# mcu_regule.net
KiCad netlist of a schematic drawn in Altium Designer
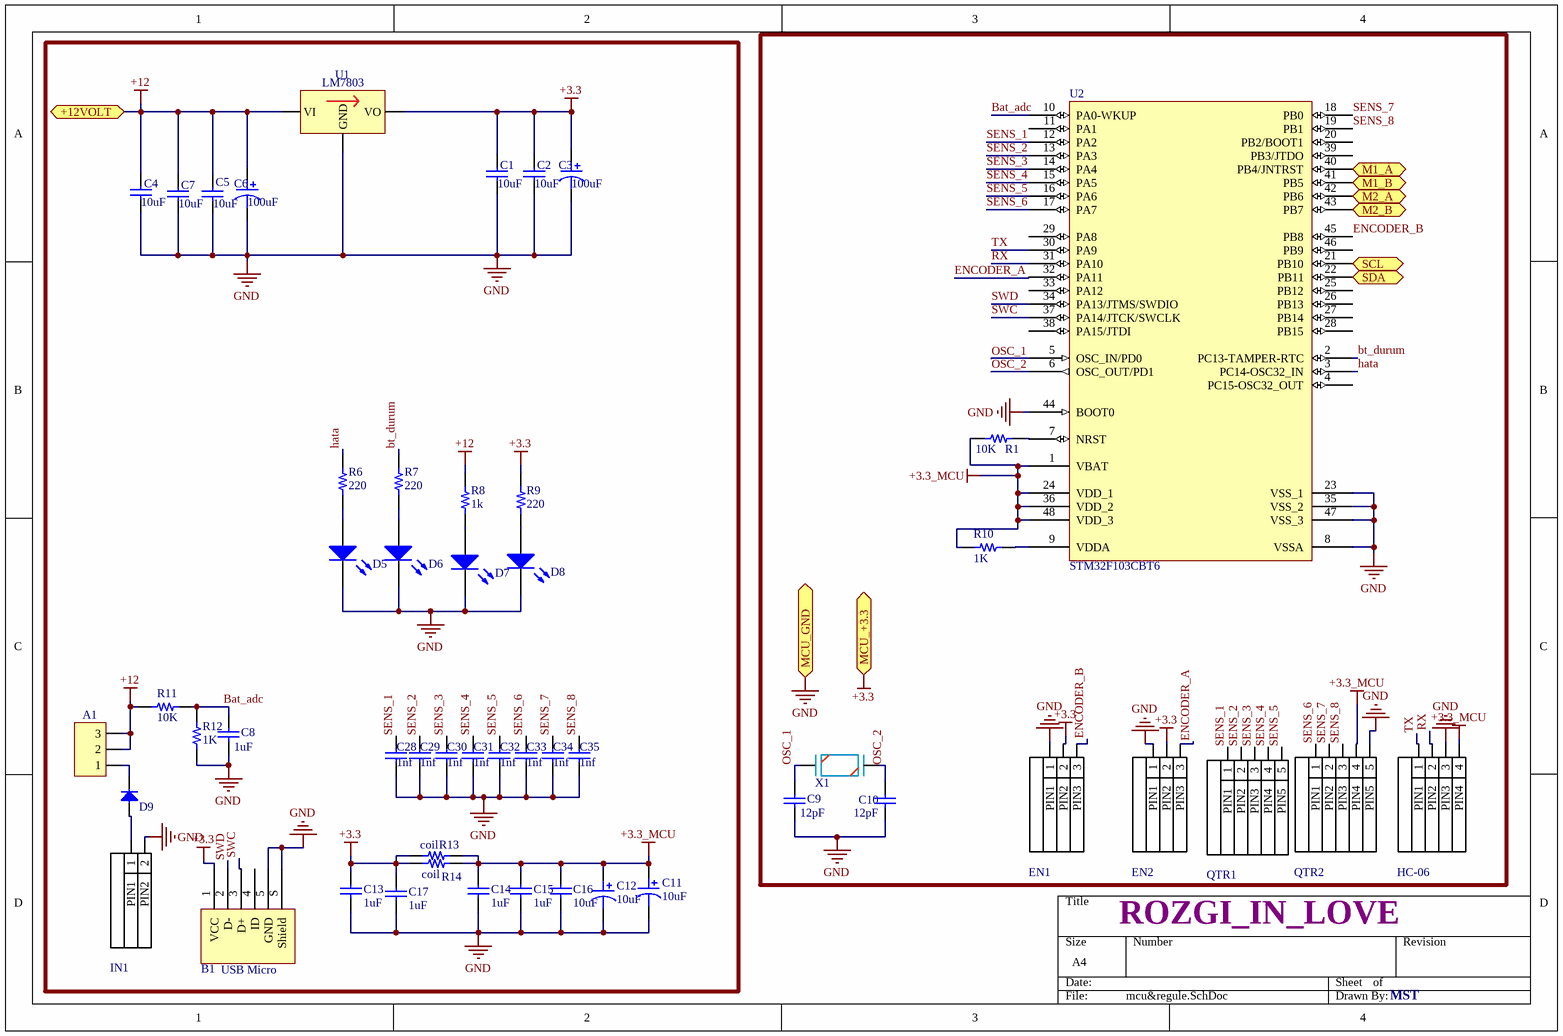
[diagram p0: mcu&regule.SchDoc]

(export (version "E")
  (design (tool "Eeschema 10.0.6"))
  (components
    (comp (ref "A1")
      (value "anahtar")
      (footprint "MSS22D18 Switch")
      (libsource (lib "genel") (part "anahtarlar"))
    )
    (comp (ref "B1")
      (value "USB Micro")
      (footprint "FCI USB 10118193-0001LF")
      (libsource (lib "genel") (part "USB 2.0 Type B Micro"))
    )
    (comp (ref "C1")
      (value "10uF")
      (footprint "Cap SMD C1206")
      (description "CAP SMD")
      (libsource (lib "genel") (part "CAP SMD THT"))
    )
    (comp (ref "C2")
      (value "10uF")
      (footprint "Cap SMD C1206")
      (description "CAP SMD")
      (libsource (lib "genel") (part "CAP SMD THT"))
    )
    (comp (ref "C3")
      (value "100uF")
      (footprint "Cap SMD ALU 6.3X6.3N")
      (description "CAP-ALU")
      (libsource (lib "genel") (part "CAP-SMD -ALU"))
    )
    (comp (ref "C4")
      (value "10uF")
      (footprint "Cap SMD C1206")
      (description "CAP SMD")
      (libsource (lib "genel") (part "CAP SMD THT"))
    )
    (comp (ref "C5")
      (value "10uF")
      (footprint "Cap SMD C1206")
      (description "CAP SMD")
      (libsource (lib "genel") (part "CAP SMD THT"))
    )
    (comp (ref "C6")
      (value "100uF")
      (footprint "Cap SMD ALU 6.3X6.3N")
      (description "CAP-ALU")
      (libsource (lib "genel") (part "CAP-SMD -ALU"))
    )
    (comp (ref "C7")
      (value "10uF")
      (footprint "Cap SMD C1206")
      (description "CAP SMD")
      (libsource (lib "genel") (part "CAP SMD THT"))
    )
    (comp (ref "C8")
      (value "1uF")
      (footprint "CAP SMD C0603")
      (description "CAP SMD")
      (libsource (lib "genel") (part "CAP SMD THT"))
    )
    (comp (ref "C9")
      (value "12pF")
      (footprint "CAP SMD C0603")
      (description "CAP SMD")
      (libsource (lib "genel") (part "CAP SMD THT"))
    )
    (comp (ref "C10")
      (value "12pF")
      (footprint "CAP SMD C0603")
      (description "CAP SMD")
      (libsource (lib "genel") (part "CAP SMD THT"))
    )
    (comp (ref "C11")
      (value "10uF")
      (footprint "Cap Tantal 3216 - Type A")
      (description "CAP-TANTAL")
      (libsource (lib "genel") (part "CAP-SMD -TANTAL"))
    )
    (comp (ref "C12")
      (value "10uF")
      (footprint "Cap Tantal 3216 - Type A")
      (description "CAP-TANTAL")
      (libsource (lib "genel") (part "CAP-SMD -TANTAL"))
    )
    (comp (ref "C13")
      (value "1uF")
      (footprint "CAP SMD C0603")
      (description "CAP SMD")
      (libsource (lib "genel") (part "CAP SMD THT"))
    )
    (comp (ref "C14")
      (value "1uF")
      (footprint "CAP SMD C0603")
      (description "CAP SMD")
      (libsource (lib "genel") (part "CAP SMD THT"))
    )
    (comp (ref "C15")
      (value "1uF")
      (footprint "CAP SMD C0603")
      (description "CAP SMD")
      (libsource (lib "genel") (part "CAP SMD THT"))
    )
    (comp (ref "C16")
      (value "10uF")
      (footprint "CAP SMD C0603")
      (description "CAP SMD")
      (libsource (lib "genel") (part "CAP SMD THT"))
    )
    (comp (ref "C17")
      (value "1uF")
      (footprint "CAP SMD C0603")
      (description "CAP SMD")
      (libsource (lib "genel") (part "CAP SMD THT"))
    )
    (comp (ref "C28")
      (value "1nf")
      (footprint "CAP SMD C0603")
      (description "CAP SMD")
      (libsource (lib "genel") (part "CAP SMD THT"))
    )
    (comp (ref "C29")
      (value "1nf")
      (footprint "CAP SMD C0603")
      (description "CAP SMD")
      (libsource (lib "genel") (part "CAP SMD THT"))
    )
    (comp (ref "C30")
      (value "1nf")
      (footprint "CAP SMD C0603")
      (description "CAP SMD")
      (libsource (lib "genel") (part "CAP SMD THT"))
    )
    (comp (ref "C31")
      (value "1nf")
      (footprint "CAP SMD C0603")
      (description "CAP SMD")
      (libsource (lib "genel") (part "CAP SMD THT"))
    )
    (comp (ref "C32")
      (value "1nf")
      (footprint "CAP SMD C0603")
      (description "CAP SMD")
      (libsource (lib "genel") (part "CAP SMD THT"))
    )
    (comp (ref "C33")
      (value "1nf")
      (footprint "CAP SMD C0603")
      (description "CAP SMD")
      (libsource (lib "genel") (part "CAP SMD THT"))
    )
    (comp (ref "C34")
      (value "1nf")
      (footprint "CAP SMD C0603")
      (description "CAP SMD")
      (libsource (lib "genel") (part "CAP SMD THT"))
    )
    (comp (ref "C35")
      (value "1nf")
      (footprint "CAP SMD C0603")
      (description "CAP SMD")
      (libsource (lib "genel") (part "CAP SMD THT"))
    )
    (comp (ref "D5")
      (value "~")
      (footprint "LED 0603/1608 GREEN")
      (description "Typical LED")
      (fields (field (name "VOLTAGE") "3V"))
      (libsource (lib "genel") (part "LED"))
    )
    (comp (ref "D6")
      (value "~")
      (footprint "LED 0603/1608 GREEN")
      (description "Typical LED")
      (fields (field (name "VOLTAGE") "3V"))
      (libsource (lib "genel") (part "LED"))
    )
    (comp (ref "D7")
      (value "~")
      (footprint "LED 0603/1608 BLUE")
      (description "Typical LED")
      (fields (field (name "VOLTAGE") "3V"))
      (libsource (lib "genel") (part "LED"))
    )
    (comp (ref "D8")
      (value "~")
      (footprint "LED 0603/1608 GREEN")
      (description "Typical LED")
      (fields (field (name "VOLTAGE") "3V"))
      (libsource (lib "genel") (part "LED"))
    )
    (comp (ref "D9")
      (value "Äèîä âûïğ ìèòåëüíûé  1N4148 (150mA 75V)  DO-35")
      (footprint "SMB, DO-214AA")
      (description "Diode")
      (fields (field (name "VOLTAGE") "75V"))
      (libsource (lib "genel") (part "Diode"))
    )
    (comp (ref "EN1")
      (value "Ğàçú¸ì PLS-3")
      (footprint "JST B3B-PH-K")
      (description "Male, 3 pin single in line, 2.54")
      (libsource (lib "header") (part "HDR 1x3"))
    )
    (comp (ref "EN2")
      (value "Ğàçú¸ì PLS-3")
      (footprint "JST B3B-PH-K")
      (description "Male, 3 pin single in line, 2.54")
      (libsource (lib "header") (part "HDR 1x3"))
    )
    (comp (ref "HC-06")
      (value "Ğàçú¸ì PLS-4")
      (footprint "JST B4B-PH-K")
      (description "Male, 4 pin single in line, 2.54")
      (libsource (lib "header") (part "HDR 1x4"))
    )
    (comp (ref "IN1")
      (value "Ğàçú¸ì PLS-2")
      (footprint "HDR1X2")
      (description "Male, 2 pin single in line, 2.54")
      (libsource (lib "header") (part "HDR 1x2"))
    )
    (comp (ref "QTR1")
      (value "Ğàçú¸ì PLS-5")
      (footprint "JST B5B-PH-K")
      (description "Male, 5 pin single in line, 2.54")
      (libsource (lib "header") (part "HDR 1x5"))
    )
    (comp (ref "QTR2")
      (value "Ğàçú¸ì PLS-5")
      (footprint "JST B5B-PH-K")
      (description "Male, 5 pin single in line, 2.54")
      (libsource (lib "header") (part "HDR 1x5"))
    )
    (comp (ref "R1")
      (value "10K")
      (footprint "RES 0603")
      (description "RES")
      (libsource (lib "genel") (part "RES"))
    )
    (comp (ref "R6")
      (value "220")
      (footprint "RES 0603")
      (description "RES")
      (libsource (lib "genel") (part "RES"))
    )
    (comp (ref "R7")
      (value "220")
      (footprint "RES 0603")
      (description "RES")
      (libsource (lib "genel") (part "RES"))
    )
    (comp (ref "R8")
      (value "1k")
      (footprint "RES 0603")
      (description "RES")
      (libsource (lib "genel") (part "RES"))
    )
    (comp (ref "R9")
      (value "220")
      (footprint "RES 0603")
      (description "RES")
      (libsource (lib "genel") (part "RES"))
    )
    (comp (ref "R10")
      (value "1K")
      (footprint "RES 0603")
      (description "RES")
      (libsource (lib "genel") (part "RES"))
    )
    (comp (ref "R11")
      (value "10K")
      (footprint "RES 0603")
      (description "RES")
      (libsource (lib "genel") (part "RES"))
    )
    (comp (ref "R12")
      (value "1K")
      (footprint "RES 0603")
      (description "RES")
      (libsource (lib "genel") (part "RES"))
    )
    (comp (ref "R13")
      (value "coil")
      (footprint "RES 0805")
      (description "RES")
      (libsource (lib "genel") (part "RES"))
    )
    (comp (ref "R14")
      (value "coil")
      (footprint "RES 0805")
      (description "RES")
      (libsource (lib "genel") (part "RES"))
    )
    (comp (ref "U1") (value "LM7803") (footprint "DPAK, TO-252-3L") (libsource (lib "genel") (part "lm7805")))
    (comp (ref "U2")
      (value "STM32F103CBT6")
      (footprint "TQFP-48_N")
      (description "STM32 ARM-based 32-bit MCU with 128 Kbytes Flash, 48-pin LQFP, Industrial Temperature")
      (fields (field (name "PUBLISHER") "Altium Limited"))
      (libsource (lib "genel") (part "STM32F103CBT6"))
    )
    (comp (ref "X1")
      (value "8MHZ XTAL")
      (footprint "ABM7  6.2 x 3.5 mm")
      (libsource (lib "genel") (part "8MHZ XTAL"))
    )
  )
  (nets
    (net (code "1") (name "+3.3") (class "Default")
      (node (ref "B1") (pin "1") (pinfunction "VCC_1") (pintype "passive"))
      (node (ref "C1") (pin "2") (pinfunction "2_2") (pintype "passive"))
      (node (ref "C13") (pin "2") (pinfunction "2_2") (pintype "passive"))
      (node (ref "C17") (pin "2") (pinfunction "2_2") (pintype "passive"))
      (node (ref "C2") (pin "2") (pinfunction "2_2") (pintype "passive"))
      (node (ref "C3") (pin "1") (pinfunction "1_1") (pintype "passive"))
      (node (ref "EN1") (pin "2") (pinfunction "PIN2_2") (pintype "passive"))
      (node (ref "EN2") (pin "2") (pinfunction "PIN2_2") (pintype "passive"))
      (node (ref "R13") (pin "1") (pinfunction "1_1") (pintype "passive"))
      (node (ref "R14") (pin "1") (pinfunction "1_1") (pintype "passive"))
      (node (ref "R9") (pin "2") (pinfunction "2_2") (pintype "passive"))
      (node (ref "U1") (pin "3") (pinfunction "VO_3") (pintype "passive"))
    )
    (net (code "2") (name "+3.3_MCU") (class "Default")
      (node (ref "C11") (pin "1") (pinfunction "1_1") (pintype "passive"))
      (node (ref "C12") (pin "1") (pinfunction "1_1") (pintype "passive"))
      (node (ref "C14") (pin "2") (pinfunction "2_2") (pintype "passive"))
      (node (ref "C15") (pin "2") (pinfunction "2_2") (pintype "passive"))
      (node (ref "C16") (pin "2") (pinfunction "2_2") (pintype "passive"))
      (node (ref "HC-06") (pin "4") (pinfunction "PIN4_4") (pintype "passive"))
      (node (ref "QTR2") (pin "4") (pinfunction "PIN4_4") (pintype "passive"))
      (node (ref "R1") (pin "1") (pinfunction "1_1") (pintype "passive"))
      (node (ref "R10") (pin "1") (pinfunction "1_1") (pintype "passive"))
      (node (ref "R13") (pin "2") (pinfunction "2_2") (pintype "passive"))
      (node (ref "R14") (pin "2") (pinfunction "2_2") (pintype "passive"))
      (node (ref "U2") (pin "1") (pinfunction "VBAT_1") (pintype "power_in"))
      (node (ref "U2") (pin "24") (pinfunction "VDD_1_24") (pintype "power_in"))
      (node (ref "U2") (pin "36") (pinfunction "VDD_2_36") (pintype "power_in"))
      (node (ref "U2") (pin "48") (pinfunction "VDD_3_48") (pintype "power_in"))
    )
    (net (code "3") (name "+12") (class "Default")
      (node (ref "A1") (pin "2") (pinfunction "2_2") (pintype "passive"))
      (node (ref "A1") (pin "3") (pinfunction "3_3") (pintype "passive"))
      (node (ref "C4") (pin "2") (pinfunction "2_2") (pintype "passive"))
      (node (ref "C5") (pin "2") (pinfunction "2_2") (pintype "passive"))
      (node (ref "C6") (pin "1") (pinfunction "1_1") (pintype "passive"))
      (node (ref "C7") (pin "2") (pinfunction "2_2") (pintype "passive"))
      (node (ref "R11") (pin "1") (pinfunction "1_1") (pintype "passive"))
      (node (ref "R8") (pin "2") (pinfunction "2_2") (pintype "passive"))
      (node (ref "U1") (pin "1") (pinfunction "VI_1") (pintype "passive"))
    )
    (net (code "4") (name "/Bat_adc") (class "Default")
      (node (ref "C8") (pin "2") (pinfunction "2_2") (pintype "passive"))
      (node (ref "R11") (pin "2") (pinfunction "2_2") (pintype "passive"))
      (node (ref "R12") (pin "2") (pinfunction "2_2") (pintype "passive"))
      (node (ref "U2") (pin "10") (pinfunction "PA0-WKUP_10") (pintype "bidirectional"))
    )
    (net (code "5") (name "/ENCODER_A") (class "Default")
      (node (ref "EN2") (pin "3") (pinfunction "PIN3_3") (pintype "passive"))
      (node (ref "U2") (pin "32") (pinfunction "PA11_32") (pintype "bidirectional"))
    )
    (net (code "6") (name "/ENCODER_B") (class "Default")
      (node (ref "EN1") (pin "3") (pinfunction "PIN3_3") (pintype "passive"))
      (node (ref "U2") (pin "45") (pinfunction "PB8_45") (pintype "bidirectional"))
    )
    (net (code "7") (name "/M1_A") (class "Default")
      (node (ref "U2") (pin "40") (pinfunction "PB4/JNTRST_40") (pintype "bidirectional"))
    )
    (net (code "8") (name "/M1_B") (class "Default")
      (node (ref "U2") (pin "41") (pinfunction "PB5_41") (pintype "bidirectional"))
    )
    (net (code "9") (name "/M2_A") (class "Default")
      (node (ref "U2") (pin "42") (pinfunction "PB6_42") (pintype "bidirectional"))
    )
    (net (code "10") (name "/M2_B") (class "Default")
      (node (ref "U2") (pin "43") (pinfunction "PB7_43") (pintype "bidirectional"))
    )
    (net (code "11") (name "/OSC_1") (class "Default")
      (node (ref "C9") (pin "2") (pinfunction "2_2") (pintype "passive"))
      (node (ref "U2") (pin "5") (pinfunction "OSC_IN/PD0_5") (pintype "input"))
      (node (ref "X1") (pin "1") (pinfunction "1_1") (pintype "passive"))
    )
    (net (code "12") (name "/OSC_2") (class "Default")
      (node (ref "C10") (pin "2") (pinfunction "2_2") (pintype "passive"))
      (node (ref "U2") (pin "6") (pinfunction "OSC_OUT/PD1_6") (pintype "output"))
      (node (ref "X1") (pin "2") (pinfunction "2_2") (pintype "passive"))
    )
    (net (code "13") (name "/RX") (class "Default")
      (node (ref "HC-06") (pin "2") (pinfunction "PIN2_2") (pintype "passive"))
      (node (ref "U2") (pin "31") (pinfunction "PA10_31") (pintype "bidirectional"))
    )
    (net (code "14") (name "/SCL") (class "Default")
      (node (ref "U2") (pin "21") (pinfunction "PB10_21") (pintype "bidirectional"))
    )
    (net (code "15") (name "/SDA") (class "Default")
      (node (ref "U2") (pin "22") (pinfunction "PB11_22") (pintype "bidirectional"))
    )
    (net (code "16") (name "/SENS_1") (class "Default")
      (node (ref "C28") (pin "2") (pinfunction "2_2") (pintype "passive"))
      (node (ref "QTR1") (pin "1") (pinfunction "PIN1_1") (pintype "passive"))
      (node (ref "U2") (pin "12") (pinfunction "PA2_12") (pintype "bidirectional"))
    )
    (net (code "17") (name "/SENS_2") (class "Default")
      (node (ref "C29") (pin "2") (pinfunction "2_2") (pintype "passive"))
      (node (ref "QTR1") (pin "2") (pinfunction "PIN2_2") (pintype "passive"))
      (node (ref "U2") (pin "13") (pinfunction "PA3_13") (pintype "bidirectional"))
    )
    (net (code "18") (name "/SENS_3") (class "Default")
      (node (ref "C30") (pin "2") (pinfunction "2_2") (pintype "passive"))
      (node (ref "QTR1") (pin "3") (pinfunction "PIN3_3") (pintype "passive"))
      (node (ref "U2") (pin "14") (pinfunction "PA4_14") (pintype "bidirectional"))
    )
    (net (code "19") (name "/SENS_4") (class "Default")
      (node (ref "C31") (pin "2") (pinfunction "2_2") (pintype "passive"))
      (node (ref "QTR1") (pin "4") (pinfunction "PIN4_4") (pintype "passive"))
      (node (ref "U2") (pin "15") (pinfunction "PA5_15") (pintype "bidirectional"))
    )
    (net (code "20") (name "/SENS_5") (class "Default")
      (node (ref "C32") (pin "2") (pinfunction "2_2") (pintype "passive"))
      (node (ref "QTR1") (pin "5") (pinfunction "PIN5_5") (pintype "passive"))
      (node (ref "U2") (pin "16") (pinfunction "PA6_16") (pintype "bidirectional"))
    )
    (net (code "21") (name "/SENS_6") (class "Default")
      (node (ref "C33") (pin "2") (pinfunction "2_2") (pintype "passive"))
      (node (ref "QTR2") (pin "1") (pinfunction "PIN1_1") (pintype "passive"))
      (node (ref "U2") (pin "17") (pinfunction "PA7_17") (pintype "bidirectional"))
    )
    (net (code "22") (name "/SENS_7") (class "Default")
      (node (ref "C34") (pin "2") (pinfunction "2_2") (pintype "passive"))
      (node (ref "QTR2") (pin "2") (pinfunction "PIN2_2") (pintype "passive"))
      (node (ref "U2") (pin "18") (pinfunction "PB0_18") (pintype "bidirectional"))
    )
    (net (code "23") (name "/SENS_8") (class "Default")
      (node (ref "C35") (pin "2") (pinfunction "2_2") (pintype "passive"))
      (node (ref "QTR2") (pin "3") (pinfunction "PIN3_3") (pintype "passive"))
      (node (ref "U2") (pin "19") (pinfunction "PB1_19") (pintype "bidirectional"))
    )
    (net (code "24") (name "/SWC") (class "Default")
      (node (ref "B1") (pin "3") (pinfunction "D+_3") (pintype "passive"))
      (node (ref "U2") (pin "37") (pinfunction "PA14/JTCK/SWCLK_37") (pintype "bidirectional"))
    )
    (net (code "25") (name "/SWD") (class "Default")
      (node (ref "B1") (pin "2") (pinfunction "D-_2") (pintype "passive"))
      (node (ref "U2") (pin "34") (pinfunction "PA13/JTMS/SWDIO_34") (pintype "bidirectional"))
    )
    (net (code "26") (name "/TX") (class "Default")
      (node (ref "HC-06") (pin "1") (pinfunction "PIN1_1") (pintype "passive"))
      (node (ref "U2") (pin "30") (pinfunction "PA9_30") (pintype "bidirectional"))
    )
    (net (code "27") (name "/bt_durum") (class "Default")
      (node (ref "R7") (pin "2") (pinfunction "2_2") (pintype "passive"))
      (node (ref "U2") (pin "2") (pinfunction "PC13-TAMPER-RTC_2") (pintype "bidirectional"))
    )
    (net (code "28") (name "/hata") (class "Default")
      (node (ref "R6") (pin "2") (pinfunction "2_2") (pintype "passive"))
      (node (ref "U2") (pin "3") (pinfunction "PC14-OSC32_IN_3") (pintype "bidirectional"))
    )
    (net (code "29") (name "GND") (class "Default")
      (node (ref "B1") (pin "5") (pinfunction "GND_5") (pintype "passive"))
      (node (ref "B1") (pin "S") (pinfunction "Shield_S") (pintype "passive"))
      (node (ref "C1") (pin "1") (pinfunction "1_1") (pintype "passive"))
      (node (ref "C10") (pin "1") (pinfunction "1_1") (pintype "passive"))
      (node (ref "C11") (pin "2") (pinfunction "2_2") (pintype "passive"))
      (node (ref "C12") (pin "2") (pinfunction "2_2") (pintype "passive"))
      (node (ref "C13") (pin "1") (pinfunction "1_1") (pintype "passive"))
      (node (ref "C14") (pin "1") (pinfunction "1_1") (pintype "passive"))
      (node (ref "C15") (pin "1") (pinfunction "1_1") (pintype "passive"))
      (node (ref "C16") (pin "1") (pinfunction "1_1") (pintype "passive"))
      (node (ref "C17") (pin "1") (pinfunction "1_1") (pintype "passive"))
      (node (ref "C2") (pin "1") (pinfunction "1_1") (pintype "passive"))
      (node (ref "C28") (pin "1") (pinfunction "1_1") (pintype "passive"))
      (node (ref "C29") (pin "1") (pinfunction "1_1") (pintype "passive"))
      (node (ref "C3") (pin "2") (pinfunction "2_2") (pintype "passive"))
      (node (ref "C30") (pin "1") (pinfunction "1_1") (pintype "passive"))
      (node (ref "C31") (pin "1") (pinfunction "1_1") (pintype "passive"))
      (node (ref "C32") (pin "1") (pinfunction "1_1") (pintype "passive"))
      (node (ref "C33") (pin "1") (pinfunction "1_1") (pintype "passive"))
      (node (ref "C34") (pin "1") (pinfunction "1_1") (pintype "passive"))
      (node (ref "C35") (pin "1") (pinfunction "1_1") (pintype "passive"))
      (node (ref "C4") (pin "1") (pinfunction "1_1") (pintype "passive"))
      (node (ref "C5") (pin "1") (pinfunction "1_1") (pintype "passive"))
      (node (ref "C6") (pin "2") (pinfunction "2_2") (pintype "passive"))
      (node (ref "C7") (pin "1") (pinfunction "1_1") (pintype "passive"))
      (node (ref "C8") (pin "1") (pinfunction "1_1") (pintype "passive"))
      (node (ref "C9") (pin "1") (pinfunction "1_1") (pintype "passive"))
      (node (ref "D5") (pin "1") (pinfunction "C_1") (pintype "passive"))
      (node (ref "D6") (pin "1") (pinfunction "C_1") (pintype "passive"))
      (node (ref "D7") (pin "1") (pinfunction "C_1") (pintype "passive"))
      (node (ref "D8") (pin "1") (pinfunction "C_1") (pintype "passive"))
      (node (ref "EN1") (pin "1") (pinfunction "PIN1_1") (pintype "passive"))
      (node (ref "EN2") (pin "1") (pinfunction "PIN1_1") (pintype "passive"))
      (node (ref "HC-06") (pin "3") (pinfunction "PIN3_3") (pintype "passive"))
      (node (ref "IN1") (pin "2") (pinfunction "PIN2_2") (pintype "passive"))
      (node (ref "QTR2") (pin "5") (pinfunction "PIN5_5") (pintype "passive"))
      (node (ref "R12") (pin "1") (pinfunction "1_1") (pintype "passive"))
      (node (ref "U1") (pin "2") (pinfunction "GND_2") (pintype "passive"))
      (node (ref "U2") (pin "23") (pinfunction "VSS_1_23") (pintype "power_in"))
      (node (ref "U2") (pin "35") (pinfunction "VSS_2_35") (pintype "power_in"))
      (node (ref "U2") (pin "44") (pinfunction "BOOT0_44") (pintype "input"))
      (node (ref "U2") (pin "47") (pinfunction "VSS_3_47") (pintype "power_in"))
      (node (ref "U2") (pin "8") (pinfunction "VSSA_8") (pintype "power_in"))
    )
    (net (code "30") (name "Net-(D5-A)") (class "Default")
      (node (ref "D5") (pin "2") (pinfunction "A_2") (pintype "passive"))
      (node (ref "R6") (pin "1") (pinfunction "1_1") (pintype "passive"))
    )
    (net (code "31") (name "Net-(D6-A)") (class "Default")
      (node (ref "D6") (pin "2") (pinfunction "A_2") (pintype "passive"))
      (node (ref "R7") (pin "1") (pinfunction "1_1") (pintype "passive"))
    )
    (net (code "32") (name "Net-(D7-A)") (class "Default")
      (node (ref "D7") (pin "2") (pinfunction "A_2") (pintype "passive"))
      (node (ref "R8") (pin "1") (pinfunction "1_1") (pintype "passive"))
    )
    (net (code "33") (name "Net-(D8-A)") (class "Default")
      (node (ref "D8") (pin "2") (pinfunction "A_2") (pintype "passive"))
      (node (ref "R9") (pin "1") (pinfunction "1_1") (pintype "passive"))
    )
    (net (code "34") (name "Net-(D9-A)") (class "Default")
      (node (ref "D9") (pin "2") (pinfunction "A_2") (pintype "passive"))
      (node (ref "IN1") (pin "1") (pinfunction "PIN1_1") (pintype "passive"))
    )
    (net (code "35") (name "Net-(D9-C)") (class "Default")
      (node (ref "A1") (pin "1") (pinfunction "1_1") (pintype "passive"))
      (node (ref "D9") (pin "1") (pinfunction "C_1") (pintype "passive"))
    )
    (net (code "36") (name "Net-(U2-NRST)") (class "Default")
      (node (ref "R1") (pin "2") (pinfunction "2_2") (pintype "passive"))
      (node (ref "U2") (pin "7") (pinfunction "NRST_7") (pintype "bidirectional"))
    )
    (net (code "37") (name "Net-(U2-VDDA)") (class "Default")
      (node (ref "R10") (pin "2") (pinfunction "2_2") (pintype "passive"))
      (node (ref "U2") (pin "9") (pinfunction "VDDA_9") (pintype "power_in"))
    )
    (net (code "38") (name "unconnected-(B1-ID-Pad4)") (class "Default")
      (node (ref "B1") (pin "4") (pinfunction "ID_4") (pintype "passive"))
    )
    (net (code "39") (name "unconnected-(U2-PA1-Pad11)") (class "Default")
      (node (ref "U2") (pin "11") (pinfunction "PA1_11") (pintype "bidirectional"))
    )
    (net (code "40") (name "unconnected-(U2-PA8-Pad29)") (class "Default")
      (node (ref "U2") (pin "29") (pinfunction "PA8_29") (pintype "bidirectional"))
    )
    (net (code "41") (name "unconnected-(U2-PA12-Pad33)") (class "Default")
      (node (ref "U2") (pin "33") (pinfunction "PA12_33") (pintype "bidirectional"))
    )
    (net (code "42") (name "unconnected-(U2-PA15{slash}JTDI-Pad38)") (class "Default")
      (node (ref "U2") (pin "38") (pinfunction "PA15/JTDI_38") (pintype "bidirectional"))
    )
    (net (code "43") (name "unconnected-(U2-PB2{slash}BOOT1-Pad20)") (class "Default")
      (node (ref "U2") (pin "20") (pinfunction "PB2/BOOT1_20") (pintype "bidirectional"))
    )
    (net (code "44") (name "unconnected-(U2-PB3{slash}JTDO-Pad39)") (class "Default")
      (node (ref "U2") (pin "39") (pinfunction "PB3/JTDO_39") (pintype "bidirectional"))
    )
    (net (code "45") (name "unconnected-(U2-PB9-Pad46)") (class "Default")
      (node (ref "U2") (pin "46") (pinfunction "PB9_46") (pintype "bidirectional"))
    )
    (net (code "46") (name "unconnected-(U2-PB12-Pad25)") (class "Default")
      (node (ref "U2") (pin "25") (pinfunction "PB12_25") (pintype "bidirectional"))
    )
    (net (code "47") (name "unconnected-(U2-PB13-Pad26)") (class "Default")
      (node (ref "U2") (pin "26") (pinfunction "PB13_26") (pintype "bidirectional"))
    )
    (net (code "48") (name "unconnected-(U2-PB14-Pad27)") (class "Default")
      (node (ref "U2") (pin "27") (pinfunction "PB14_27") (pintype "bidirectional"))
    )
    (net (code "49") (name "unconnected-(U2-PB15-Pad28)") (class "Default")
      (node (ref "U2") (pin "28") (pinfunction "PB15_28") (pintype "bidirectional"))
    )
    (net (code "50") (name "unconnected-(U2-PC15-OSC32_OUT-Pad4)") (class "Default")
      (node (ref "U2") (pin "4") (pinfunction "PC15-OSC32_OUT_4") (pintype "bidirectional"))
    )
  )
)
